# SCH_usb-hub-v1_2024-01-11.net
KiCad netlist of a schematic drawn in EasyEDA
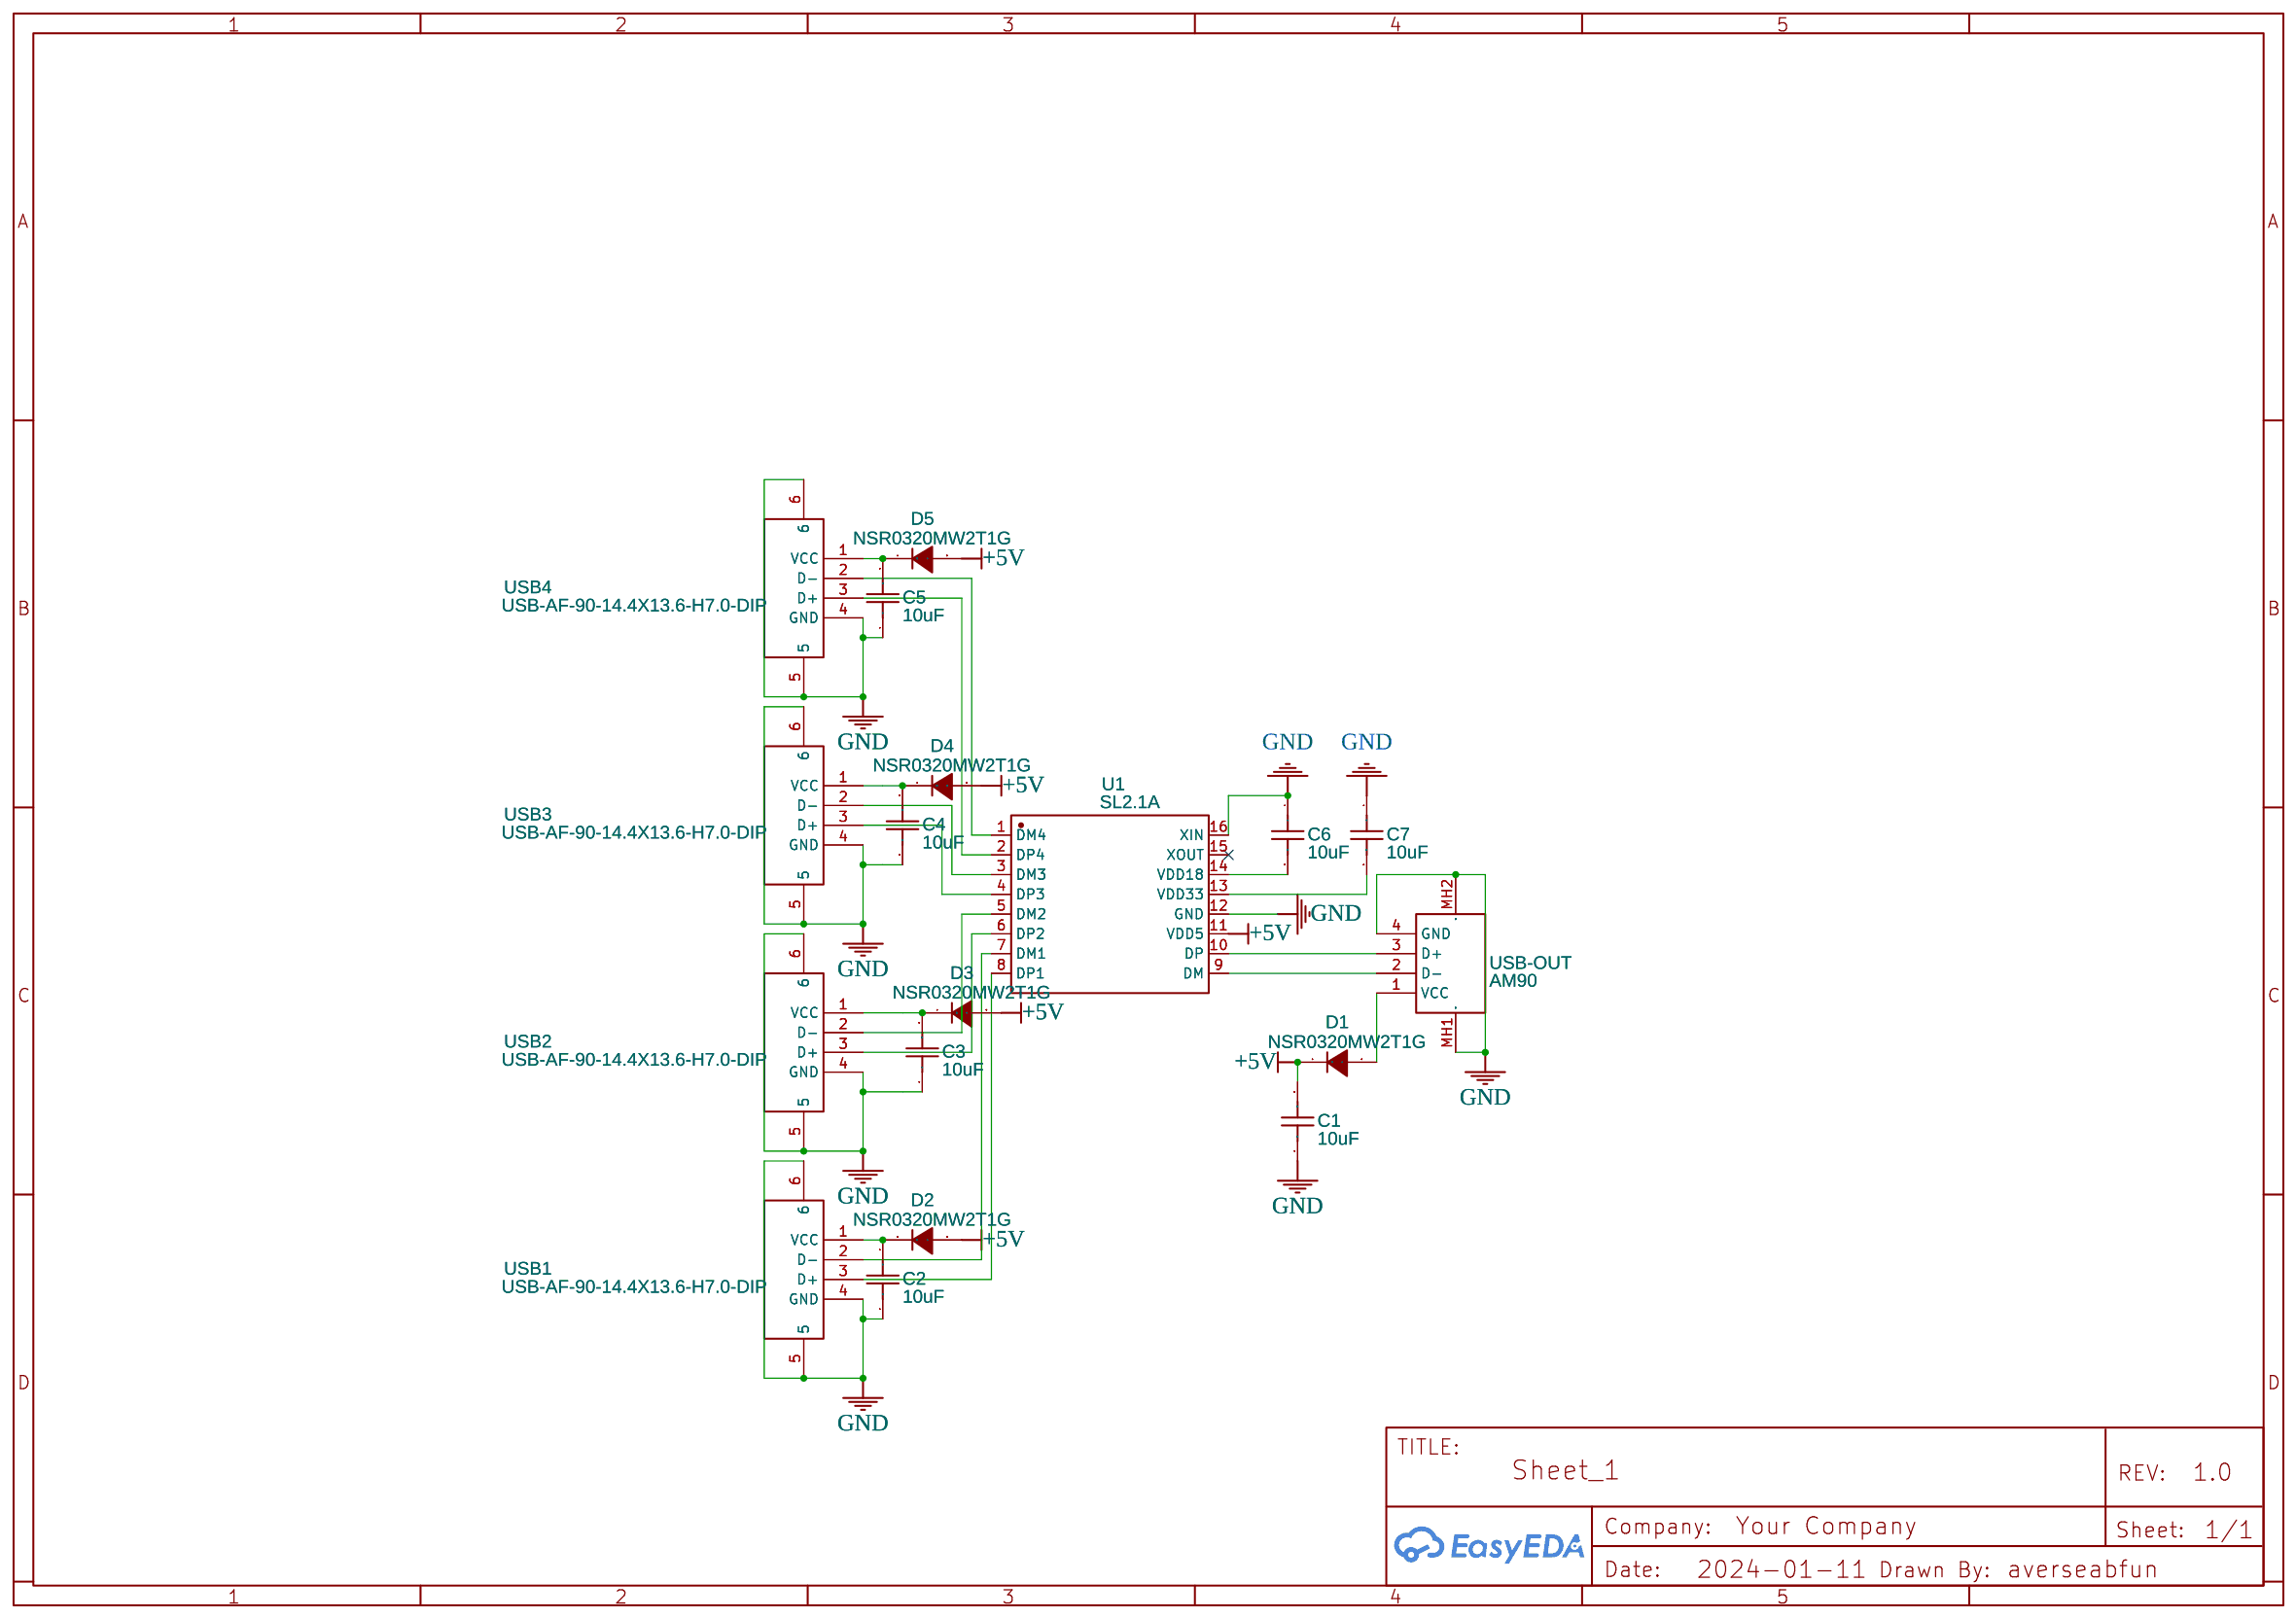
[diagram p0: schematic sheet]

(export (version "E")
  (design (tool "Eeschema 10.0.6"))
  (components
    (comp (ref "C1")
      (value "10uF")
      (fields
        (field (name "Manufacturer Part") "CL10A106KP8NNNC")
        (field (name "Manufacturer") "SAMSUNG(三星)")
      )
      (libsource (lib "") (part "CL10A106KP8NNNC"))
    )
    (comp (ref "C2")
      (value "10uF")
      (fields
        (field (name "Manufacturer Part") "CL10A106KP8NNNC")
        (field (name "Manufacturer") "SAMSUNG(三星)")
      )
      (libsource (lib "") (part "CL10A106KP8NNNC"))
    )
    (comp (ref "C3")
      (value "10uF")
      (fields
        (field (name "Manufacturer Part") "CL10A106KP8NNNC")
        (field (name "Manufacturer") "SAMSUNG(三星)")
      )
      (libsource (lib "") (part "CL10A106KP8NNNC"))
    )
    (comp (ref "C4")
      (value "10uF")
      (fields
        (field (name "Manufacturer Part") "CL10A106KP8NNNC")
        (field (name "Manufacturer") "SAMSUNG(三星)")
      )
      (libsource (lib "") (part "CL10A106KP8NNNC"))
    )
    (comp (ref "C5")
      (value "10uF")
      (fields
        (field (name "Manufacturer Part") "CL10A106KP8NNNC")
        (field (name "Manufacturer") "SAMSUNG(三星)")
      )
      (libsource (lib "") (part "CL10A106KP8NNNC"))
    )
    (comp (ref "C6")
      (value "10uF")
      (fields
        (field (name "Manufacturer Part") "CL10A106KP8NNNC")
        (field (name "Manufacturer") "SAMSUNG(三星)")
      )
      (libsource (lib "") (part "CL10A106KP8NNNC_1"))
    )
    (comp (ref "C7")
      (value "10uF")
      (fields
        (field (name "Manufacturer Part") "CL10A106KP8NNNC")
        (field (name "Manufacturer") "SAMSUNG(三星)")
      )
      (libsource (lib "") (part "CL10A106KP8NNNC_1"))
    )
    (comp (ref "D1")
      (value "NSR0320MW2T1G")
      (fields (field (name "Manufacturer") "onsemi(安森美)"))
      (libsource (lib "") (part "NSR0320MW2T1G"))
    )
    (comp (ref "D2")
      (value "NSR0320MW2T1G")
      (fields (field (name "Manufacturer") "onsemi(安森美)"))
      (libsource (lib "") (part "NSR0320MW2T1G"))
    )
    (comp (ref "D3")
      (value "NSR0320MW2T1G")
      (fields (field (name "Manufacturer") "onsemi(安森美)"))
      (libsource (lib "") (part "NSR0320MW2T1G"))
    )
    (comp (ref "D4")
      (value "NSR0320MW2T1G")
      (fields (field (name "Manufacturer") "onsemi(安森美)"))
      (libsource (lib "") (part "NSR0320MW2T1G"))
    )
    (comp (ref "D5")
      (value "NSR0320MW2T1G")
      (fields (field (name "Manufacturer") "onsemi(安森美)"))
      (libsource (lib "") (part "NSR0320MW2T1G"))
    )
    (comp (ref "U1")
      (value "SL2.1A")
      (fields (field (name "Manufacturer") "CoreChips(和芯润德)"))
      (libsource (lib "") (part "SL2.1A"))
    )
    (comp (ref "USB-OUT")
      (value "AM90")
      (fields (field (name "Manufacturer") "SHOU HAN(首韩)"))
      (libsource (lib "") (part "AM90"))
    )
    (comp (ref "USB1")
      (value "USB-AF-90-14.4X13.6-H7.0-DIP")
      (fields (field (name "Manufacturer Part") "903-131A1011D10100") (field (name "Manufacturer") "精拓金"))
      (libsource (lib "") (part "USB-AF-90-14.4X13.6-H7.0-DIP"))
    )
    (comp (ref "USB2")
      (value "USB-AF-90-14.4X13.6-H7.0-DIP")
      (fields (field (name "Manufacturer Part") "903-131A1011D10100") (field (name "Manufacturer") "精拓金"))
      (libsource (lib "") (part "USB-AF-90-14.4X13.6-H7.0-DIP"))
    )
    (comp (ref "USB3")
      (value "USB-AF-90-14.4X13.6-H7.0-DIP")
      (fields (field (name "Manufacturer Part") "903-131A1011D10100") (field (name "Manufacturer") "精拓金"))
      (libsource (lib "") (part "USB-AF-90-14.4X13.6-H7.0-DIP"))
    )
    (comp (ref "USB4")
      (value "USB-AF-90-14.4X13.6-H7.0-DIP")
      (fields (field (name "Manufacturer Part") "903-131A1011D10100") (field (name "Manufacturer") "精拓金"))
      (libsource (lib "") (part "USB-AF-90-14.4X13.6-H7.0-DIP"))
    )
  )
  (nets
    (net (code "1") (name "+5V") (class "Default")
      (node (ref "C1") (pin "2") (pinfunction "2_2") (pintype "unspecified"))
      (node (ref "D1") (pin "1") (pinfunction "C_1") (pintype "unspecified"))
      (node (ref "D2") (pin "2") (pinfunction "A_2") (pintype "unspecified"))
      (node (ref "D3") (pin "2") (pinfunction "A_2") (pintype "unspecified"))
      (node (ref "D4") (pin "2") (pinfunction "A_2") (pintype "unspecified"))
      (node (ref "D5") (pin "2") (pinfunction "A_2") (pintype "unspecified"))
      (node (ref "U1") (pin "11") (pinfunction "VDD5_11") (pintype "unspecified"))
    )
    (net (code "2") (name "GND") (class "Default")
      (node (ref "C1") (pin "1") (pinfunction "1_1") (pintype "unspecified"))
      (node (ref "C2") (pin "1") (pinfunction "1_1") (pintype "unspecified"))
      (node (ref "C3") (pin "1") (pinfunction "1_1") (pintype "unspecified"))
      (node (ref "C4") (pin "1") (pinfunction "1_1") (pintype "unspecified"))
      (node (ref "C5") (pin "1") (pinfunction "1_1") (pintype "unspecified"))
      (node (ref "C6") (pin "1") (pinfunction "1_1") (pintype "unspecified"))
      (node (ref "C7") (pin "1") (pinfunction "1_1") (pintype "unspecified"))
      (node (ref "U1") (pin "12") (pinfunction "GND_12") (pintype "unspecified"))
      (node (ref "U1") (pin "16") (pinfunction "XIN_16") (pintype "unspecified"))
      (node (ref "USB-OUT") (pin "4") (pinfunction "GND_4") (pintype "input"))
      (node (ref "USB-OUT") (pin "MH1") (pinfunction "MH1_MH1") (pintype "unspecified"))
      (node (ref "USB-OUT") (pin "MH2") (pinfunction "MH2_MH2") (pintype "unspecified"))
      (node (ref "USB1") (pin "4") (pinfunction "GND_4") (pintype "unspecified"))
      (node (ref "USB1") (pin "5") (pinfunction "5_5") (pintype "unspecified"))
      (node (ref "USB1") (pin "6") (pinfunction "6_6") (pintype "unspecified"))
      (node (ref "USB2") (pin "4") (pinfunction "GND_4") (pintype "unspecified"))
      (node (ref "USB2") (pin "5") (pinfunction "5_5") (pintype "unspecified"))
      (node (ref "USB2") (pin "6") (pinfunction "6_6") (pintype "unspecified"))
      (node (ref "USB3") (pin "4") (pinfunction "GND_4") (pintype "unspecified"))
      (node (ref "USB3") (pin "5") (pinfunction "5_5") (pintype "unspecified"))
      (node (ref "USB3") (pin "6") (pinfunction "6_6") (pintype "unspecified"))
      (node (ref "USB4") (pin "4") (pinfunction "GND_4") (pintype "unspecified"))
      (node (ref "USB4") (pin "5") (pinfunction "5_5") (pintype "unspecified"))
      (node (ref "USB4") (pin "6") (pinfunction "6_6") (pintype "unspecified"))
    )
    (net (code "3") (name "Net-(D1-A)") (class "Default")
      (node (ref "D1") (pin "2") (pinfunction "A_2") (pintype "unspecified"))
      (node (ref "USB-OUT") (pin "1") (pinfunction "VCC_1") (pintype "input"))
    )
    (net (code "4") (name "Net-(D2-C)") (class "Default")
      (node (ref "C2") (pin "2") (pinfunction "2_2") (pintype "unspecified"))
      (node (ref "D2") (pin "1") (pinfunction "C_1") (pintype "unspecified"))
      (node (ref "USB1") (pin "1") (pinfunction "VCC_1") (pintype "unspecified"))
    )
    (net (code "5") (name "Net-(D3-C)") (class "Default")
      (node (ref "C3") (pin "2") (pinfunction "2_2") (pintype "unspecified"))
      (node (ref "D3") (pin "1") (pinfunction "C_1") (pintype "unspecified"))
      (node (ref "USB2") (pin "1") (pinfunction "VCC_1") (pintype "unspecified"))
    )
    (net (code "6") (name "Net-(D4-C)") (class "Default")
      (node (ref "C4") (pin "2") (pinfunction "2_2") (pintype "unspecified"))
      (node (ref "D4") (pin "1") (pinfunction "C_1") (pintype "unspecified"))
      (node (ref "USB3") (pin "1") (pinfunction "VCC_1") (pintype "unspecified"))
    )
    (net (code "7") (name "Net-(D5-C)") (class "Default")
      (node (ref "C5") (pin "2") (pinfunction "2_2") (pintype "unspecified"))
      (node (ref "D5") (pin "1") (pinfunction "C_1") (pintype "unspecified"))
      (node (ref "USB4") (pin "1") (pinfunction "VCC_1") (pintype "unspecified"))
    )
    (net (code "8") (name "Net-(U1-DM)") (class "Default")
      (node (ref "U1") (pin "9") (pinfunction "DM_9") (pintype "unspecified"))
      (node (ref "USB-OUT") (pin "2") (pinfunction "D-_2") (pintype "input"))
    )
    (net (code "9") (name "Net-(U1-DM1)") (class "Default")
      (node (ref "U1") (pin "7") (pinfunction "DM1_7") (pintype "unspecified"))
      (node (ref "USB1") (pin "2") (pinfunction "D-_2") (pintype "unspecified"))
    )
    (net (code "10") (name "Net-(U1-DM2)") (class "Default")
      (node (ref "U1") (pin "5") (pinfunction "DM2_5") (pintype "unspecified"))
      (node (ref "USB2") (pin "2") (pinfunction "D-_2") (pintype "unspecified"))
    )
    (net (code "11") (name "Net-(U1-DM3)") (class "Default")
      (node (ref "U1") (pin "3") (pinfunction "DM3_3") (pintype "unspecified"))
      (node (ref "USB3") (pin "2") (pinfunction "D-_2") (pintype "unspecified"))
    )
    (net (code "12") (name "Net-(U1-DM4)") (class "Default")
      (node (ref "U1") (pin "1") (pinfunction "DM4_1") (pintype "unspecified"))
      (node (ref "USB4") (pin "2") (pinfunction "D-_2") (pintype "unspecified"))
    )
    (net (code "13") (name "Net-(U1-DP)") (class "Default")
      (node (ref "U1") (pin "10") (pinfunction "DP_10") (pintype "unspecified"))
      (node (ref "USB-OUT") (pin "3") (pinfunction "D+_3") (pintype "input"))
    )
    (net (code "14") (name "Net-(U1-DP1)") (class "Default")
      (node (ref "U1") (pin "8") (pinfunction "DP1_8") (pintype "unspecified"))
      (node (ref "USB1") (pin "3") (pinfunction "D+_3") (pintype "unspecified"))
    )
    (net (code "15") (name "Net-(U1-DP2)") (class "Default")
      (node (ref "U1") (pin "6") (pinfunction "DP2_6") (pintype "unspecified"))
      (node (ref "USB2") (pin "3") (pinfunction "D+_3") (pintype "unspecified"))
    )
    (net (code "16") (name "Net-(U1-DP3)") (class "Default")
      (node (ref "U1") (pin "4") (pinfunction "DP3_4") (pintype "unspecified"))
      (node (ref "USB3") (pin "3") (pinfunction "D+_3") (pintype "unspecified"))
    )
    (net (code "17") (name "Net-(U1-DP4)") (class "Default")
      (node (ref "U1") (pin "2") (pinfunction "DP4_2") (pintype "unspecified"))
      (node (ref "USB4") (pin "3") (pinfunction "D+_3") (pintype "unspecified"))
    )
    (net (code "18") (name "Net-(U1-VDD18)") (class "Default")
      (node (ref "C6") (pin "2") (pinfunction "2_2") (pintype "unspecified"))
      (node (ref "U1") (pin "14") (pinfunction "VDD18_14") (pintype "unspecified"))
    )
    (net (code "19") (name "Net-(U1-VDD33)") (class "Default")
      (node (ref "C7") (pin "2") (pinfunction "2_2") (pintype "unspecified"))
      (node (ref "U1") (pin "13") (pinfunction "VDD33_13") (pintype "unspecified"))
    )
    (net (code "20") (name "unconnected-(U1-XOUT-Pad15)") (class "Default")
      (node (ref "U1") (pin "15") (pinfunction "XOUT_15") (pintype "unspecified+no_connect"))
    )
  )
)
